# 01-POWER.net
KiCad netlist of a schematic drawn in Altium Designer
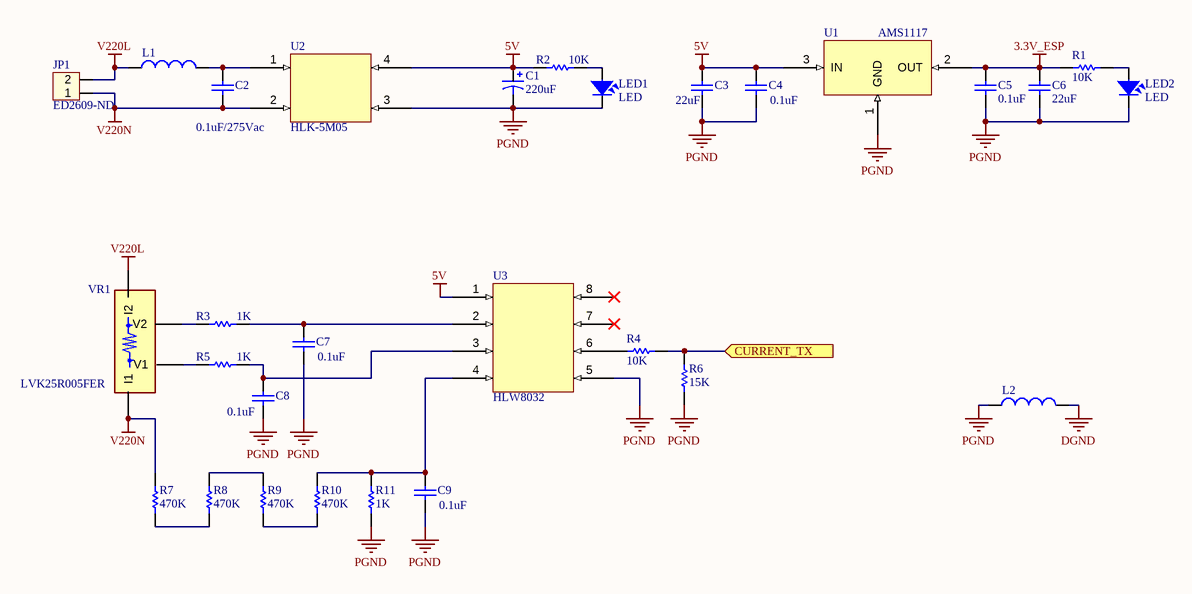
[diagram p0: 01-POWER.SchDoc]

(export (version "E")
  (design (tool "Eeschema 10.0.6"))
  (components
    (comp (ref "C1")
      (value "220uF")
      (footprint "CAP ALU CASE G SMD")
      (description "CAP ALU 220UF 20% 50V SMD")
      (fields
        (field (name "MANUFACTURER") "Nichicon")
        (field (name "MANUFACTURER PART NUMBER") "UPW1J331MHD")
      )
      (libsource (lib "GSHT_181013") (part "330uF/50V/ALU12.5X20mm/20%/7000Hrs"))
    )
    (comp (ref "C2")
      (value "0.1uF/275Vac")
      (footprint "FilM_Cap")
      (description "0.1 µF Film Capacitor 275V - Polypropylene (PP), Metallized Radial")
      (fields (field (name "MANUFACTURER") "Murata"))
      (libsource (lib "GSHT_181013") (part "0.1uF/50V/C0603/10%"))
    )
    (comp (ref "C3")
      (value "22uF")
      (footprint "CAP_CERA_C2012(CC0805INCH)")
      (description "22µF ±20% 25V Ceramic Capacitor X5R 0805 (2012 Metric)")
      (fields (field (name "MANUFACTURER") "Tariff Applied"))
      (libsource (lib "GSHT_181013") (part "0.1uF/50V/C0603/10%"))
    )
    (comp (ref "C4")
      (value "0.1uF")
      (footprint "CAP_CERA_C2012(CC0805INCH)")
      (description "0.1µF ±10% 25V Ceramic Capacitor X7R 0805 (2012 Metric)")
      (libsource (lib "GSHT_181013") (part "0.1uF/50V/C0603/10%"))
    )
    (comp (ref "C5")
      (value "0.1uF")
      (footprint "CAP_CERA_C2012(CC0805INCH)")
      (description "0.1µF ±10% 25V Ceramic Capacitor X7R 0805 (2012 Metric)")
      (libsource (lib "GSHT_181013") (part "0.1uF/50V/C0603/10%"))
    )
    (comp (ref "C6")
      (value "22uF")
      (footprint "CAP_CERA_C2012(CC0805INCH)")
      (description "22µF ±20% 25V Ceramic Capacitor X5R 0805 (2012 Metric)")
      (fields (field (name "MANUFACTURER") "Tariff Applied"))
      (libsource (lib "GSHT_181013") (part "0.1uF/50V/C0603/10%"))
    )
    (comp (ref "C7")
      (value "0.1uF")
      (footprint "Cap Ceramic 0603 SMD")
      (description "CAP CER 0.1UF 50V 10% X7R 0603")
      (fields
        (field (name "MANUFACTURER") "Murata Electronics North America")
        (field (name "MANUFACTURER PART NUMBER") "GRM188R71H104KA93D")
      )
      (libsource (lib "GSHT_181013") (part "0.1uF/50V/C0603/10%"))
    )
    (comp (ref "C8")
      (value "0.1uF")
      (footprint "Cap Ceramic 0603 SMD")
      (description "CAP CER 0.1UF 50V 10% X7R 0603")
      (fields
        (field (name "MANUFACTURER") "Murata Electronics North America")
        (field (name "MANUFACTURER PART NUMBER") "GRM188R71H104KA93D")
      )
      (libsource (lib "GSHT_181013") (part "0.1uF/50V/C0603/10%"))
    )
    (comp (ref "C9")
      (value "0.1uF")
      (footprint "Cap Ceramic 0603 SMD")
      (description "CAP CER 0.1UF 50V 10% X7R 0603")
      (fields
        (field (name "MANUFACTURER") "Murata Electronics North America")
        (field (name "MANUFACTURER PART NUMBER") "GRM188R71H104KA93D")
      )
      (libsource (lib "GSHT_181013") (part "0.1uF/50V/C0603/10%"))
    )
    (comp (ref "JP1")
      (value "ED2609-ND")
      (footprint "DOMINO_OSTTC_2P")
      (description "2 Position Wire to Board Terminal Block Horizontal with Board 0.200\" (5.08mm) Through Hole")
      (libsource (lib "lpson") (part "Con2"))
    )
    (comp (ref "L1")
      (value "744212820")
      (footprint "WE-SL1")
      (description "Sensible value10-15mH，current\r\n70-500mA")
      (libsource (lib "lpson") (part "Inductor"))
    )
    (comp (ref "L2")
      (value "ASPI-7318-8R2M-TCT-ND")
      (footprint "ASPI-7318-8R2M-TCT-ND")
      (description "Sensible value10-15mH，current\r\n70-500mA")
      (libsource (lib "lpson") (part "Inductor"))
    )
    (comp (ref "LED1")
      (value "LED")
      (footprint "Led 0805G")
      (description "LED Single colour Green and Red")
      (libsource (lib "lpson") (part "LED"))
    )
    (comp (ref "LED2")
      (value "LED")
      (footprint "Led 0805G")
      (description "LED Single colour Green and Red")
      (libsource (lib "lpson") (part "LED"))
    )
    (comp (ref "R1")
      (value "10K")
      (footprint "Res 0603 SMD")
      (description "RES SMD 10K OHM 1% 1/10W 0603")
      (fields
        (field (name "MANUFACTURER") "Yageo")
        (field (name "MANUFACTURER PART NUMBER") "RC0603FR-0715KL")
      )
      (libsource (lib "GSHT_181013") (part "15K/R0603/1%"))
    )
    (comp (ref "R2")
      (value "10K")
      (footprint "Res 0603 SMD")
      (description "RES SMD 10K OHM 1% 1/10W 0603")
      (fields
        (field (name "MANUFACTURER") "Yageo")
        (field (name "MANUFACTURER PART NUMBER") "RC0603FR-0715KL")
      )
      (libsource (lib "GSHT_181013") (part "15K/R0603/1%"))
    )
    (comp (ref "R3")
      (value "1K")
      (footprint "Res 0603 SMD")
      (description "RES SMD 1K OHM 1% 1/10W 0603")
      (fields
        (field (name "MANUFACTURER") "Yageo")
        (field (name "MANUFACTURER PART NUMBER") "RC0603FR-0715KL")
      )
      (libsource (lib "GSHT_181013") (part "15K/R0603/1%"))
    )
    (comp (ref "R4")
      (value "10K")
      (footprint "Res 0603 SMD")
      (description "RES SMD 10K OHM 1% 1/10W 0603")
      (fields
        (field (name "MANUFACTURER") "Yageo")
        (field (name "MANUFACTURER PART NUMBER") "RC0603FR-0715KL")
      )
      (libsource (lib "GSHT_181013") (part "15K/R0603/1%"))
    )
    (comp (ref "R5")
      (value "1K")
      (footprint "Res 0603 SMD")
      (description "RES SMD 1K OHM 1% 1/10W 0603")
      (fields
        (field (name "MANUFACTURER") "Yageo")
        (field (name "MANUFACTURER PART NUMBER") "RC0603FR-0715KL")
      )
      (libsource (lib "GSHT_181013") (part "15K/R0603/1%"))
    )
    (comp (ref "R6")
      (value "15K")
      (footprint "Res 0603 SMD")
      (description "RES SMD 15K OHM 1% 1/10W 0603")
      (fields
        (field (name "MANUFACTURER") "Yageo")
        (field (name "MANUFACTURER PART NUMBER") "RC0603FR-0715KL")
      )
      (libsource (lib "GSHT_181013") (part "15K/R0603/1%"))
    )
    (comp (ref "R7")
      (value "470K")
      (footprint "Res 0603 SMD")
      (description "RES SMD 470K OHM 1% 1/10W 0603")
      (fields
        (field (name "MANUFACTURER") "Yageo")
        (field (name "MANUFACTURER PART NUMBER") "RC0603FR-0715KL")
      )
      (libsource (lib "GSHT_181013") (part "15K/R0603/1%"))
    )
    (comp (ref "R8")
      (value "470K")
      (footprint "Res 0603 SMD")
      (description "RES SMD 470K OHM 1% 1/10W 0603")
      (fields
        (field (name "MANUFACTURER") "Yageo")
        (field (name "MANUFACTURER PART NUMBER") "RC0603FR-0715KL")
      )
      (libsource (lib "GSHT_181013") (part "15K/R0603/1%"))
    )
    (comp (ref "R9")
      (value "470K")
      (footprint "Res 0603 SMD")
      (description "RES SMD 470K OHM 1% 1/10W 0603")
      (fields
        (field (name "MANUFACTURER") "Yageo")
        (field (name "MANUFACTURER PART NUMBER") "RC0603FR-0715KL")
      )
      (libsource (lib "GSHT_181013") (part "15K/R0603/1%"))
    )
    (comp (ref "R10")
      (value "470K")
      (footprint "Res 0603 SMD")
      (description "RES SMD 470K OHM 1% 1/10W 0603")
      (fields
        (field (name "MANUFACTURER") "Yageo")
        (field (name "MANUFACTURER PART NUMBER") "RC0603FR-0715KL")
      )
      (libsource (lib "GSHT_181013") (part "15K/R0603/1%"))
    )
    (comp (ref "R11")
      (value "1K")
      (footprint "Res 0603 SMD")
      (description "RES SMD 1K OHM 1% 1/10W 0603")
      (fields
        (field (name "MANUFACTURER") "Yageo")
        (field (name "MANUFACTURER PART NUMBER") "RC0603FR-0715KL")
      )
      (libsource (lib "GSHT_181013") (part "15K/R0603/1%"))
    )
    (comp (ref "U1")
      (value "AMS1117")
      (footprint "SOT230P700X180-4N")
      (libsource (lib "Schlib1") (part "AMS1117"))
    )
    (comp (ref "U2")
      (value "HLK-5M05")
      (footprint "CONV_HLK-5M05")
      (libsource (lib "Schlib1") (part "HLK-5M05"))
    )
    (comp (ref "U3")
      (value "HLW8032")
      (footprint "SOIC127P600X175-8N")
      (libsource (lib "Schlib1") (part "HLW8032"))
    )
    (comp (ref "VR1")
      (value "LVK25R005FER")
      (footprint "LVK25R005FER")
      (description "Resistor")
      (fields
        (field (name "MOUSER PART NUMBER") "588-LVK25R005FER")
        (field (name "RS PART NUMBER") "8934005")
      )
      (libsource (lib "MySchlib") (part "LVK25R005FER"))
    )
  )
  (nets
    (net (code "1") (name "/CURRENT_TX") (class "Default")
      (node (ref "R4") (pin "2") (pinfunction "2_2") (pintype "passive"))
      (node (ref "R6") (pin "1") (pinfunction "1_1") (pintype "passive"))
    )
    (net (code "2") (name "3.3V_ESP") (class "Default")
      (node (ref "C5") (pin "2") (pinfunction "2_2") (pintype "passive"))
      (node (ref "C6") (pin "2") (pinfunction "2_2") (pintype "passive"))
      (node (ref "R1") (pin "1") (pinfunction "1_1") (pintype "passive"))
      (node (ref "U1") (pin "2") (pinfunction "OUT_2") (pintype "input"))
    )
    (net (code "3") (name "5V") (class "Default")
      (node (ref "C1") (pin "1") (pinfunction "1_1") (pintype "passive"))
      (node (ref "C3") (pin "2") (pinfunction "2_2") (pintype "passive"))
      (node (ref "C4") (pin "2") (pinfunction "2_2") (pintype "passive"))
      (node (ref "R2") (pin "1") (pinfunction "1_1") (pintype "passive"))
      (node (ref "U1") (pin "3") (pinfunction "IN_3") (pintype "input"))
      (node (ref "U2") (pin "4") (pintype "input"))
      (node (ref "U3") (pin "1") (pintype "input"))
    )
    (net (code "4") (name "DGND") (class "Default")
      (node (ref "L2") (pin "2") (pinfunction "2_2") (pintype "passive"))
    )
    (net (code "5") (name "Net-(C2-Pad2)") (class "Default")
      (node (ref "C2") (pin "2") (pinfunction "2_2") (pintype "passive"))
      (node (ref "L1") (pin "2") (pinfunction "2_2") (pintype "passive"))
      (node (ref "U2") (pin "1") (pintype "input"))
    )
    (net (code "6") (name "Net-(C7-Pad2)") (class "Default")
      (node (ref "C7") (pin "2") (pinfunction "2_2") (pintype "passive"))
      (node (ref "R3") (pin "1") (pinfunction "1_1") (pintype "passive"))
      (node (ref "U3") (pin "2") (pintype "input"))
    )
    (net (code "7") (name "Net-(C8-Pad2)") (class "Default")
      (node (ref "C8") (pin "2") (pinfunction "2_2") (pintype "passive"))
      (node (ref "R5") (pin "1") (pinfunction "1_1") (pintype "passive"))
      (node (ref "U3") (pin "3") (pintype "input"))
    )
    (net (code "8") (name "Net-(C9-Pad2)") (class "Default")
      (node (ref "C9") (pin "2") (pinfunction "2_2") (pintype "passive"))
      (node (ref "R10") (pin "1") (pinfunction "1_1") (pintype "passive"))
      (node (ref "R11") (pin "2") (pinfunction "2_2") (pintype "passive"))
      (node (ref "U3") (pin "4") (pintype "input"))
    )
    (net (code "9") (name "Net-(LED1-Pad1)") (class "Default")
      (node (ref "LED1") (pin "1") (pinfunction "1_1") (pintype "passive"))
      (node (ref "R2") (pin "2") (pinfunction "2_2") (pintype "passive"))
    )
    (net (code "10") (name "Net-(LED2-Pad1)") (class "Default")
      (node (ref "LED2") (pin "1") (pinfunction "1_1") (pintype "passive"))
      (node (ref "R1") (pin "2") (pinfunction "2_2") (pintype "passive"))
    )
    (net (code "11") (name "Net-(R4-Pad1)") (class "Default")
      (node (ref "R4") (pin "1") (pinfunction "1_1") (pintype "passive"))
      (node (ref "U3") (pin "6") (pintype "input"))
    )
    (net (code "12") (name "Net-(R7-Pad2)") (class "Default")
      (node (ref "R7") (pin "2") (pinfunction "2_2") (pintype "passive"))
      (node (ref "R8") (pin "2") (pinfunction "2_2") (pintype "passive"))
    )
    (net (code "13") (name "Net-(R8-Pad1)") (class "Default")
      (node (ref "R8") (pin "1") (pinfunction "1_1") (pintype "passive"))
      (node (ref "R9") (pin "1") (pinfunction "1_1") (pintype "passive"))
    )
    (net (code "14") (name "Net-(R10-Pad2)") (class "Default")
      (node (ref "R10") (pin "2") (pinfunction "2_2") (pintype "passive"))
      (node (ref "R9") (pin "2") (pinfunction "2_2") (pintype "passive"))
    )
    (net (code "15") (name "Net-(VR1-V1)") (class "Default")
      (node (ref "R5") (pin "2") (pinfunction "2_2") (pintype "passive"))
      (node (ref "VR1") (pin "3") (pinfunction "V1_3") (pintype "passive"))
    )
    (net (code "16") (name "Net-(VR1-V2)") (class "Default")
      (node (ref "R3") (pin "2") (pinfunction "2_2") (pintype "passive"))
      (node (ref "VR1") (pin "4") (pinfunction "V2_4") (pintype "passive"))
    )
    (net (code "17") (name "PGND") (class "Default")
      (node (ref "C1") (pin "2") (pinfunction "2_2") (pintype "passive"))
      (node (ref "C3") (pin "1") (pinfunction "1_1") (pintype "passive"))
      (node (ref "C4") (pin "1") (pinfunction "1_1") (pintype "passive"))
      (node (ref "C5") (pin "1") (pinfunction "1_1") (pintype "passive"))
      (node (ref "C6") (pin "1") (pinfunction "1_1") (pintype "passive"))
      (node (ref "C7") (pin "1") (pinfunction "1_1") (pintype "passive"))
      (node (ref "C8") (pin "1") (pinfunction "1_1") (pintype "passive"))
      (node (ref "C9") (pin "1") (pinfunction "1_1") (pintype "passive"))
      (node (ref "L2") (pin "1") (pinfunction "1_1") (pintype "passive"))
      (node (ref "LED1") (pin "2") (pinfunction "2_2") (pintype "passive"))
      (node (ref "LED2") (pin "2") (pinfunction "2_2") (pintype "passive"))
      (node (ref "R11") (pin "1") (pinfunction "1_1") (pintype "passive"))
      (node (ref "R6") (pin "2") (pinfunction "2_2") (pintype "passive"))
      (node (ref "U1") (pin "1") (pinfunction "GND_1") (pintype "input"))
      (node (ref "U2") (pin "3") (pintype "input"))
      (node (ref "U3") (pin "5") (pintype "input"))
    )
    (net (code "18") (name "V220L") (class "Default")
      (node (ref "JP1") (pin "2") (pinfunction "2_2") (pintype "passive"))
      (node (ref "L1") (pin "1") (pinfunction "1_1") (pintype "passive"))
      (node (ref "VR1") (pin "2") (pinfunction "I2_2") (pintype "passive"))
    )
    (net (code "19") (name "V220N") (class "Default")
      (node (ref "C2") (pin "1") (pinfunction "1_1") (pintype "passive"))
      (node (ref "JP1") (pin "1") (pinfunction "1_1") (pintype "passive"))
      (node (ref "R7") (pin "1") (pinfunction "1_1") (pintype "passive"))
      (node (ref "U2") (pin "2") (pintype "input"))
      (node (ref "VR1") (pin "1") (pinfunction "I1_1") (pintype "passive"))
    )
    (net (code "20") (name "unconnected-(U3-Pad7)") (class "Default")
      (node (ref "U3") (pin "7") (pintype "input+no_connect"))
    )
    (net (code "21") (name "unconnected-(U3-Pad8)") (class "Default")
      (node (ref "U3") (pin "8") (pintype "input+no_connect"))
    )
  )
)
